# doppelshift2Bus.net
KiCad netlist of a schematic drawn in EAGLE
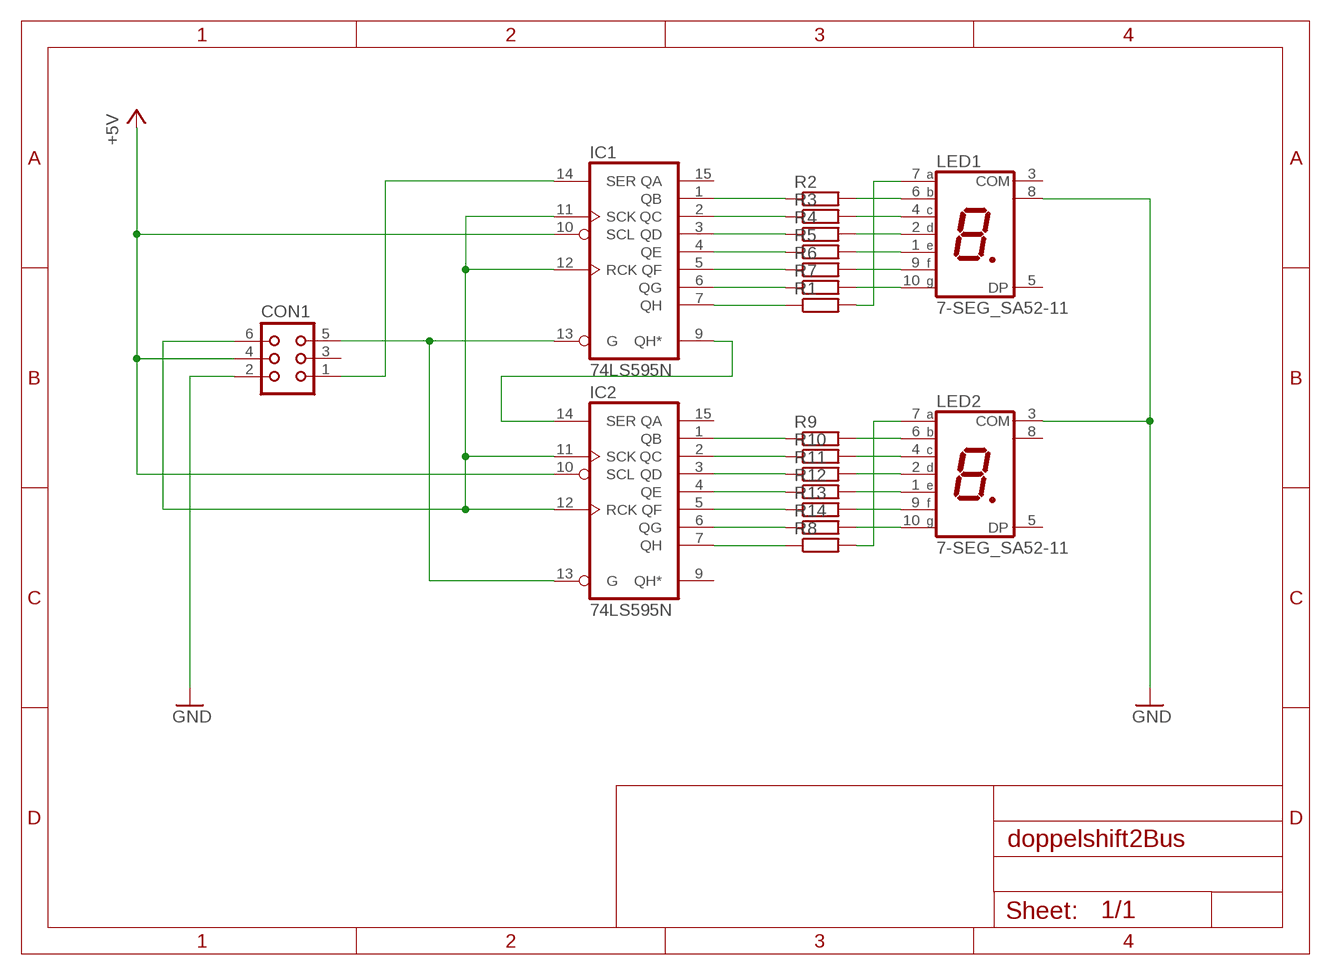
[diagram p0: schematic, sheet 1]

(export (version "E")
  (design (tool "Eeschema 10.0.6"))
  (components
    (comp (ref "CON1")
      (value "CON06L")
      (footprint "eagle-import:CON06L")
      (libsource (lib "eagle-import") (part "CON06L"))
    )
    (comp (ref "IC1")
      (value "74LS595N")
      (footprint "eagle-import:DIL16")
      (libsource (lib "eagle-import") (part "74595NLS"))
    )
    (comp (ref "IC2")
      (value "74LS595N")
      (footprint "eagle-import:DIL16")
      (libsource (lib "eagle-import") (part "74595NLS"))
    )
    (comp (ref "LED1")
      (value "7-SEG_SA52-11")
      (footprint "eagle-import:SA52-11")
      (libsource (lib "eagle-import") (part "7-SEG_SA52-11"))
    )
    (comp (ref "LED2")
      (value "7-SEG_SA52-11")
      (footprint "eagle-import:SA52-11")
      (libsource (lib "eagle-import") (part "7-SEG_SA52-11"))
    )
    (comp (ref "R1")
      (value "R-EU_0309/10")
      (footprint "eagle-import:0309_10")
      (libsource (lib "eagle-import") (part "R-EU_0309/10"))
    )
    (comp (ref "R2")
      (value "R-EU_0309/10")
      (footprint "eagle-import:0309_10")
      (libsource (lib "eagle-import") (part "R-EU_0309/10"))
    )
    (comp (ref "R3")
      (value "R-EU_0309/10")
      (footprint "eagle-import:0309_10")
      (libsource (lib "eagle-import") (part "R-EU_0309/10"))
    )
    (comp (ref "R4")
      (value "R-EU_0309/10")
      (footprint "eagle-import:0309_10")
      (libsource (lib "eagle-import") (part "R-EU_0309/10"))
    )
    (comp (ref "R5")
      (value "R-EU_0309/10")
      (footprint "eagle-import:0309_10")
      (libsource (lib "eagle-import") (part "R-EU_0309/10"))
    )
    (comp (ref "R6")
      (value "R-EU_0309/10")
      (footprint "eagle-import:0309_10")
      (libsource (lib "eagle-import") (part "R-EU_0309/10"))
    )
    (comp (ref "R7")
      (value "R-EU_0309/10")
      (footprint "eagle-import:0309_10")
      (libsource (lib "eagle-import") (part "R-EU_0309/10"))
    )
    (comp (ref "R8")
      (value "R-EU_0309/10")
      (footprint "eagle-import:0309_10")
      (libsource (lib "eagle-import") (part "R-EU_0309/10"))
    )
    (comp (ref "R9")
      (value "R-EU_0309/10")
      (footprint "eagle-import:0309_10")
      (libsource (lib "eagle-import") (part "R-EU_0309/10"))
    )
    (comp (ref "R10")
      (value "R-EU_0309/10")
      (footprint "eagle-import:0309_10")
      (libsource (lib "eagle-import") (part "R-EU_0309/10"))
    )
    (comp (ref "R11")
      (value "R-EU_0309/10")
      (footprint "eagle-import:0309_10")
      (libsource (lib "eagle-import") (part "R-EU_0309/10"))
    )
    (comp (ref "R12")
      (value "R-EU_0309/10")
      (footprint "eagle-import:0309_10")
      (libsource (lib "eagle-import") (part "R-EU_0309/10"))
    )
    (comp (ref "R13")
      (value "R-EU_0309/10")
      (footprint "eagle-import:0309_10")
      (libsource (lib "eagle-import") (part "R-EU_0309/10"))
    )
    (comp (ref "R14")
      (value "R-EU_0309/10")
      (footprint "eagle-import:0309_10")
      (libsource (lib "eagle-import") (part "R-EU_0309/10"))
    )
  )
  (nets
    (net (code "1") (name "+5V") (class "Default")
      (node (ref "CON1") (pin "4") (pinfunction "4_4") (pintype "passive"))
      (node (ref "IC1") (pin "10") (pinfunction "SCL_10") (pintype "input"))
      (node (ref "IC2") (pin "10") (pinfunction "SCL_10") (pintype "input"))
    )
    (net (code "2") (name "GND") (class "Default")
      (node (ref "CON1") (pin "2") (pinfunction "2_2") (pintype "passive"))
      (node (ref "LED1") (pin "8") (pinfunction "COM_8") (pintype "passive"))
      (node (ref "LED2") (pin "3") (pinfunction "COM_3") (pintype "passive"))
    )
    (net (code "3") (name "Net-(IC1A-G)") (class "Default")
      (node (ref "CON1") (pin "5") (pinfunction "5_5") (pintype "passive"))
      (node (ref "IC1") (pin "13") (pinfunction "G_13") (pintype "input"))
      (node (ref "IC2") (pin "13") (pinfunction "G_13") (pintype "input"))
    )
    (net (code "4") (name "Net-(IC1A-QB)") (class "Default")
      (node (ref "IC1") (pin "1") (pinfunction "QB_1") (pintype "tri_state"))
      (node (ref "R2") (pin "1") (pinfunction "1_1") (pintype "passive"))
    )
    (net (code "5") (name "Net-(IC1A-QC)") (class "Default")
      (node (ref "IC1") (pin "2") (pinfunction "QC_2") (pintype "tri_state"))
      (node (ref "R3") (pin "1") (pinfunction "1_1") (pintype "passive"))
    )
    (net (code "6") (name "Net-(IC1A-QD)") (class "Default")
      (node (ref "IC1") (pin "3") (pinfunction "QD_3") (pintype "tri_state"))
      (node (ref "R4") (pin "1") (pinfunction "1_1") (pintype "passive"))
    )
    (net (code "7") (name "Net-(IC1A-QE)") (class "Default")
      (node (ref "IC1") (pin "4") (pinfunction "QE_4") (pintype "tri_state"))
      (node (ref "R5") (pin "1") (pinfunction "1_1") (pintype "passive"))
    )
    (net (code "8") (name "Net-(IC1A-QF)") (class "Default")
      (node (ref "IC1") (pin "5") (pinfunction "QF_5") (pintype "tri_state"))
      (node (ref "R6") (pin "1") (pinfunction "1_1") (pintype "passive"))
    )
    (net (code "9") (name "Net-(IC1A-QG)") (class "Default")
      (node (ref "IC1") (pin "6") (pinfunction "QG_6") (pintype "tri_state"))
      (node (ref "R7") (pin "1") (pinfunction "1_1") (pintype "passive"))
    )
    (net (code "10") (name "Net-(IC1A-QH)") (class "Default")
      (node (ref "IC1") (pin "7") (pinfunction "QH_7") (pintype "tri_state"))
      (node (ref "R1") (pin "1") (pinfunction "1_1") (pintype "passive"))
    )
    (net (code "11") (name "Net-(IC1A-QH*)") (class "Default")
      (node (ref "IC1") (pin "9") (pinfunction "QH*_9") (pintype "tri_state"))
      (node (ref "IC2") (pin "14") (pinfunction "SER_14") (pintype "input"))
    )
    (net (code "12") (name "Net-(IC1A-RCK)") (class "Default")
      (node (ref "CON1") (pin "6") (pinfunction "6_6") (pintype "passive"))
      (node (ref "IC1") (pin "11") (pinfunction "SCK_11") (pintype "input"))
      (node (ref "IC1") (pin "12") (pinfunction "RCK_12") (pintype "input"))
      (node (ref "IC2") (pin "11") (pinfunction "SCK_11") (pintype "input"))
      (node (ref "IC2") (pin "12") (pinfunction "RCK_12") (pintype "input"))
    )
    (net (code "13") (name "Net-(IC1A-SER)") (class "Default")
      (node (ref "CON1") (pin "1") (pinfunction "1_1") (pintype "passive"))
      (node (ref "IC1") (pin "14") (pinfunction "SER_14") (pintype "input"))
    )
    (net (code "14") (name "Net-(IC2A-QB)") (class "Default")
      (node (ref "IC2") (pin "1") (pinfunction "QB_1") (pintype "tri_state"))
      (node (ref "R9") (pin "1") (pinfunction "1_1") (pintype "passive"))
    )
    (net (code "15") (name "Net-(IC2A-QC)") (class "Default")
      (node (ref "IC2") (pin "2") (pinfunction "QC_2") (pintype "tri_state"))
      (node (ref "R10") (pin "1") (pinfunction "1_1") (pintype "passive"))
    )
    (net (code "16") (name "Net-(IC2A-QD)") (class "Default")
      (node (ref "IC2") (pin "3") (pinfunction "QD_3") (pintype "tri_state"))
      (node (ref "R11") (pin "1") (pinfunction "1_1") (pintype "passive"))
    )
    (net (code "17") (name "Net-(IC2A-QE)") (class "Default")
      (node (ref "IC2") (pin "4") (pinfunction "QE_4") (pintype "tri_state"))
      (node (ref "R12") (pin "1") (pinfunction "1_1") (pintype "passive"))
    )
    (net (code "18") (name "Net-(IC2A-QF)") (class "Default")
      (node (ref "IC2") (pin "5") (pinfunction "QF_5") (pintype "tri_state"))
      (node (ref "R13") (pin "1") (pinfunction "1_1") (pintype "passive"))
    )
    (net (code "19") (name "Net-(IC2A-QG)") (class "Default")
      (node (ref "IC2") (pin "6") (pinfunction "QG_6") (pintype "tri_state"))
      (node (ref "R14") (pin "1") (pinfunction "1_1") (pintype "passive"))
    )
    (net (code "20") (name "Net-(IC2A-QH)") (class "Default")
      (node (ref "IC2") (pin "7") (pinfunction "QH_7") (pintype "tri_state"))
      (node (ref "R8") (pin "1") (pinfunction "1_1") (pintype "passive"))
    )
    (net (code "21") (name "Net-(LED1-A)") (class "Default")
      (node (ref "LED1") (pin "7") (pinfunction "A_7") (pintype "passive"))
      (node (ref "R1") (pin "2") (pinfunction "2_2") (pintype "passive"))
    )
    (net (code "22") (name "Net-(LED1-B)") (class "Default")
      (node (ref "LED1") (pin "6") (pinfunction "B_6") (pintype "passive"))
      (node (ref "R2") (pin "2") (pinfunction "2_2") (pintype "passive"))
    )
    (net (code "23") (name "Net-(LED1-C)") (class "Default")
      (node (ref "LED1") (pin "4") (pinfunction "C_4") (pintype "passive"))
      (node (ref "R3") (pin "2") (pinfunction "2_2") (pintype "passive"))
    )
    (net (code "24") (name "Net-(LED1-D)") (class "Default")
      (node (ref "LED1") (pin "2") (pinfunction "D_2") (pintype "passive"))
      (node (ref "R4") (pin "2") (pinfunction "2_2") (pintype "passive"))
    )
    (net (code "25") (name "Net-(LED1-E)") (class "Default")
      (node (ref "LED1") (pin "1") (pinfunction "E_1") (pintype "passive"))
      (node (ref "R5") (pin "2") (pinfunction "2_2") (pintype "passive"))
    )
    (net (code "26") (name "Net-(LED1-F)") (class "Default")
      (node (ref "LED1") (pin "9") (pinfunction "F_9") (pintype "passive"))
      (node (ref "R6") (pin "2") (pinfunction "2_2") (pintype "passive"))
    )
    (net (code "27") (name "Net-(LED1-G)") (class "Default")
      (node (ref "LED1") (pin "10") (pinfunction "G_10") (pintype "passive"))
      (node (ref "R7") (pin "2") (pinfunction "2_2") (pintype "passive"))
    )
    (net (code "28") (name "Net-(LED2-A)") (class "Default")
      (node (ref "LED2") (pin "7") (pinfunction "A_7") (pintype "passive"))
      (node (ref "R8") (pin "2") (pinfunction "2_2") (pintype "passive"))
    )
    (net (code "29") (name "Net-(LED2-B)") (class "Default")
      (node (ref "LED2") (pin "6") (pinfunction "B_6") (pintype "passive"))
      (node (ref "R9") (pin "2") (pinfunction "2_2") (pintype "passive"))
    )
    (net (code "30") (name "Net-(LED2-C)") (class "Default")
      (node (ref "LED2") (pin "4") (pinfunction "C_4") (pintype "passive"))
      (node (ref "R10") (pin "2") (pinfunction "2_2") (pintype "passive"))
    )
    (net (code "31") (name "Net-(LED2-D)") (class "Default")
      (node (ref "LED2") (pin "2") (pinfunction "D_2") (pintype "passive"))
      (node (ref "R11") (pin "2") (pinfunction "2_2") (pintype "passive"))
    )
    (net (code "32") (name "Net-(LED2-E)") (class "Default")
      (node (ref "LED2") (pin "1") (pinfunction "E_1") (pintype "passive"))
      (node (ref "R12") (pin "2") (pinfunction "2_2") (pintype "passive"))
    )
    (net (code "33") (name "Net-(LED2-F)") (class "Default")
      (node (ref "LED2") (pin "9") (pinfunction "F_9") (pintype "passive"))
      (node (ref "R13") (pin "2") (pinfunction "2_2") (pintype "passive"))
    )
    (net (code "34") (name "Net-(LED2-G)") (class "Default")
      (node (ref "LED2") (pin "10") (pinfunction "G_10") (pintype "passive"))
      (node (ref "R14") (pin "2") (pinfunction "2_2") (pintype "passive"))
    )
    (net (code "35") (name "unconnected-(CON1-Pad3)") (class "Default")
      (node (ref "CON1") (pin "3") (pinfunction "3_3") (pintype "passive"))
    )
    (net (code "36") (name "unconnected-(IC1A-QA-Pad15)") (class "Default")
      (node (ref "IC1") (pin "15") (pinfunction "QA_15") (pintype "tri_state"))
    )
    (net (code "37") (name "unconnected-(IC2A-QA-Pad15)") (class "Default")
      (node (ref "IC2") (pin "15") (pinfunction "QA_15") (pintype "tri_state"))
    )
    (net (code "38") (name "unconnected-(IC2A-QH*-Pad9)") (class "Default")
      (node (ref "IC2") (pin "9") (pinfunction "QH*_9") (pintype "tri_state"))
    )
    (net (code "39") (name "unconnected-(LED1-COM-Pad3)") (class "Default")
      (node (ref "LED1") (pin "3") (pinfunction "COM_3") (pintype "passive"))
    )
    (net (code "40") (name "unconnected-(LED1-DP-Pad5)") (class "Default")
      (node (ref "LED1") (pin "5") (pinfunction "DP_5") (pintype "passive"))
    )
    (net (code "41") (name "unconnected-(LED2-COM-Pad8)") (class "Default")
      (node (ref "LED2") (pin "8") (pinfunction "COM_8") (pintype "passive"))
    )
    (net (code "42") (name "unconnected-(LED2-DP-Pad5)") (class "Default")
      (node (ref "LED2") (pin "5") (pinfunction "DP_5") (pintype "passive"))
    )
  )
)
